# Kalibracija4.net
KiCad netlist of a schematic drawn in Altium Designer
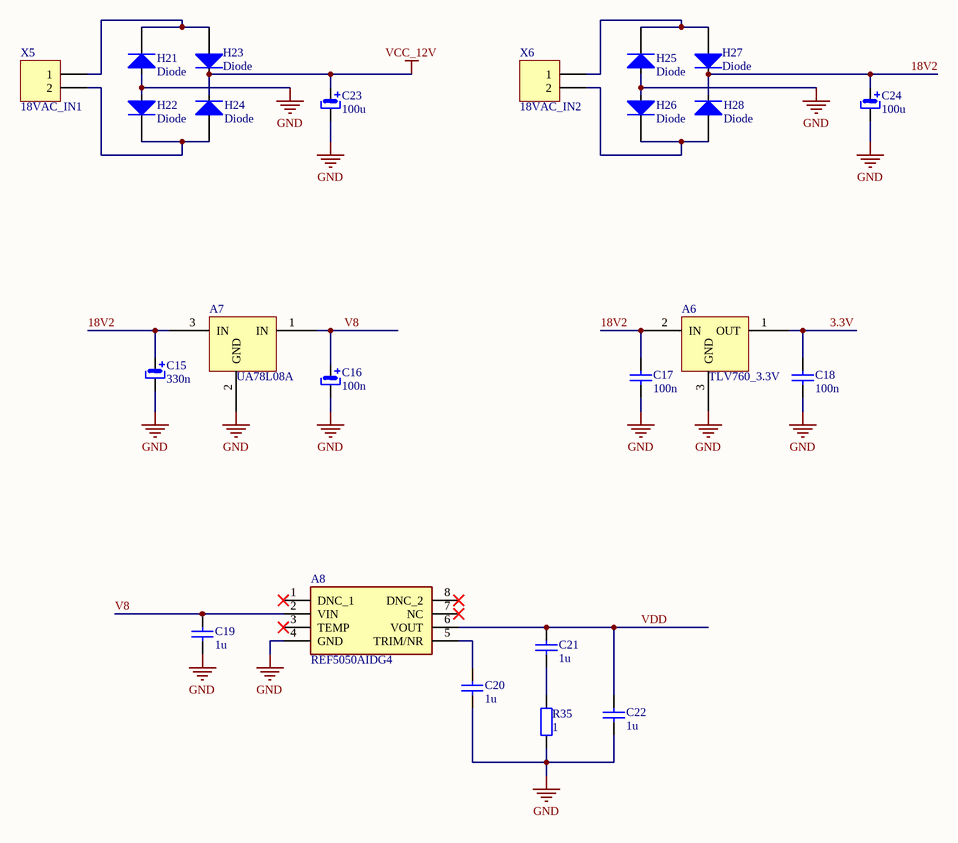
[diagram p0: Kalibracija4.SchDoc]

(export (version "E")
  (design (tool "Eeschema 10.0.6"))
  (components
    (comp (ref "A6") (value "TLV760_3.3V") (libsource (lib "Kalibracija") (part "TLV760")))
    (comp (ref "A7") (value "UA78L08A") (footprint "TO-92") (libsource (lib "Kalibracija") (part "UA78L08A")))
    (comp (ref "A8")
      (value "REF5050AIDG4")
      (footprint "SamacSys:SOIC127P600X175-8N")
      (description "Integrated Circuit")
      (fields (field (name "MOUSER PART NUMBER") "595-REF5050AIDG4"))
      (libsource (lib "*") (part "REF5050AIDG4"))
    )
    (comp (ref "C15") (value "330n") (libsource (lib "Kalibracija") (part "elko")))
    (comp (ref "C16") (value "100n") (libsource (lib "Kalibracija") (part "elko")))
    (comp (ref "C17")
      (value "100n")
      (footprint "6-0805_N")
      (description "Capacitor")
      (fields (field (name "PUBLISHER") "Altium Limited"))
      (libsource (lib "Miscellaneous Devices") (part "Cap"))
    )
    (comp (ref "C18")
      (value "100n")
      (footprint "6-0805_N")
      (description "Capacitor")
      (fields (field (name "PUBLISHER") "Altium Limited"))
      (libsource (lib "Miscellaneous Devices") (part "Cap"))
    )
    (comp (ref "C19")
      (value "1u")
      (footprint "6-0805_N")
      (description "Capacitor")
      (fields (field (name "PUBLISHER") "Altium Limited"))
      (libsource (lib "Miscellaneous Devices") (part "Cap"))
    )
    (comp (ref "C20")
      (value "1u")
      (footprint "6-0805_N")
      (description "Capacitor")
      (fields (field (name "PUBLISHER") "Altium Limited"))
      (libsource (lib "Miscellaneous Devices") (part "Cap"))
    )
    (comp (ref "C21")
      (value "1u")
      (footprint "6-0805_N")
      (description "Capacitor")
      (fields (field (name "PUBLISHER") "Altium Limited"))
      (libsource (lib "Miscellaneous Devices") (part "Cap"))
    )
    (comp (ref "C22")
      (value "1u")
      (footprint "6-0805_N")
      (description "Capacitor")
      (fields (field (name "PUBLISHER") "Altium Limited"))
      (libsource (lib "Miscellaneous Devices") (part "Cap"))
    )
    (comp (ref "C23") (value "100u") (libsource (lib "Kalibracija") (part "elko")))
    (comp (ref "C24") (value "100u") (libsource (lib "Kalibracija") (part "elko")))
    (comp (ref "H21")
      (value "Diode")
      (footprint "SMC")
      (description "Default Diode")
      (fields (field (name "PUBLISHER") "Altium Limited"))
      (libsource (lib "Miscellaneous Devices") (part "Diode"))
    )
    (comp (ref "H22")
      (value "Diode")
      (footprint "SMC")
      (description "Default Diode")
      (fields (field (name "PUBLISHER") "Altium Limited"))
      (libsource (lib "Miscellaneous Devices") (part "Diode"))
    )
    (comp (ref "H23")
      (value "Diode")
      (footprint "SMC")
      (description "Default Diode")
      (fields (field (name "PUBLISHER") "Altium Limited"))
      (libsource (lib "Miscellaneous Devices") (part "Diode"))
    )
    (comp (ref "H24")
      (value "Diode")
      (footprint "SMC")
      (description "Default Diode")
      (fields (field (name "PUBLISHER") "Altium Limited"))
      (libsource (lib "Miscellaneous Devices") (part "Diode"))
    )
    (comp (ref "H25")
      (value "Diode")
      (footprint "SMC")
      (description "Default Diode")
      (fields (field (name "PUBLISHER") "Altium Limited"))
      (libsource (lib "Miscellaneous Devices") (part "Diode"))
    )
    (comp (ref "H26")
      (value "Diode")
      (footprint "SMC")
      (description "Default Diode")
      (fields (field (name "PUBLISHER") "Altium Limited"))
      (libsource (lib "Miscellaneous Devices") (part "Diode"))
    )
    (comp (ref "H27")
      (value "Diode")
      (footprint "SMC")
      (description "Default Diode")
      (fields (field (name "PUBLISHER") "Altium Limited"))
      (libsource (lib "Miscellaneous Devices") (part "Diode"))
    )
    (comp (ref "H28")
      (value "Diode")
      (footprint "SMC")
      (description "Default Diode")
      (fields (field (name "PUBLISHER") "Altium Limited"))
      (libsource (lib "Miscellaneous Devices") (part "Diode"))
    )
    (comp (ref "R35")
      (value "1")
      (footprint "6-0805_N")
      (description "Resistor")
      (fields (field (name "PUBLISHER") "Altium Limited"))
      (libsource (lib "Miscellaneous Devices") (part "Res2"))
    )
    (comp (ref "X5")
      (value "18VAC_IN1")
      (footprint "HDR1X2")
      (description "Header, 2-Pin, Right Angle")
      (fields (field (name "PUBLISHER") "Altium Limited"))
      (libsource (lib "Miscellaneous Connectors") (part "Header 2H"))
    )
    (comp (ref "X6")
      (value "18VAC_IN2")
      (footprint "HDR1X2")
      (description "Header, 2-Pin, Right Angle")
      (fields (field (name "PUBLISHER") "Altium Limited"))
      (libsource (lib "Miscellaneous Connectors") (part "Header 2H"))
    )
  )
  (nets
    (net (code "1") (name "/3.3V") (class "Default")
      (node (ref "A6") (pin "1") (pinfunction "OUT_1") (pintype "power_in"))
      (node (ref "C18") (pin "2") (pinfunction "2_2") (pintype "passive"))
    )
    (net (code "2") (name "/18V2") (class "Default")
      (node (ref "A6") (pin "2") (pinfunction "IN_2") (pintype "passive"))
      (node (ref "A7") (pin "3") (pinfunction "IN_3") (pintype "power_in"))
      (node (ref "C15") (pin "1") (pinfunction "1_1") (pintype "passive"))
      (node (ref "C17") (pin "2") (pinfunction "2_2") (pintype "passive"))
      (node (ref "C24") (pin "1") (pinfunction "1_1") (pintype "passive"))
      (node (ref "H27") (pin "2") (pinfunction "K_2") (pintype "passive"))
      (node (ref "H28") (pin "2") (pinfunction "K_2") (pintype "passive"))
    )
    (net (code "3") (name "/V8") (class "Default")
      (node (ref "A7") (pin "1") (pinfunction "IN_1") (pintype "passive"))
      (node (ref "A8") (pin "2") (pinfunction "VIN_2") (pintype "passive"))
      (node (ref "C16") (pin "1") (pinfunction "1_1") (pintype "passive"))
      (node (ref "C19") (pin "2") (pinfunction "2_2") (pintype "passive"))
    )
    (net (code "4") (name "/VDD") (class "Default")
      (node (ref "A8") (pin "6") (pinfunction "VOUT_6") (pintype "passive"))
      (node (ref "C21") (pin "2") (pinfunction "2_2") (pintype "passive"))
      (node (ref "C22") (pin "2") (pinfunction "2_2") (pintype "passive"))
    )
    (net (code "5") (name "GND") (class "Default")
      (node (ref "A6") (pin "3") (pinfunction "GND_3") (pintype "power_in"))
      (node (ref "A7") (pin "2") (pinfunction "GND_2") (pintype "power_in"))
      (node (ref "A8") (pin "4") (pinfunction "GND_4") (pintype "passive"))
      (node (ref "C15") (pin "2") (pinfunction "2_2") (pintype "passive"))
      (node (ref "C16") (pin "2") (pinfunction "2_2") (pintype "passive"))
      (node (ref "C17") (pin "1") (pinfunction "1_1") (pintype "passive"))
      (node (ref "C18") (pin "1") (pinfunction "1_1") (pintype "passive"))
      (node (ref "C19") (pin "1") (pinfunction "1_1") (pintype "passive"))
      (node (ref "C20") (pin "1") (pinfunction "1_1") (pintype "passive"))
      (node (ref "C22") (pin "1") (pinfunction "1_1") (pintype "passive"))
      (node (ref "C23") (pin "2") (pinfunction "2_2") (pintype "passive"))
      (node (ref "C24") (pin "2") (pinfunction "2_2") (pintype "passive"))
      (node (ref "H21") (pin "1") (pinfunction "A_1") (pintype "passive"))
      (node (ref "H22") (pin "1") (pinfunction "A_1") (pintype "passive"))
      (node (ref "H25") (pin "1") (pinfunction "A_1") (pintype "passive"))
      (node (ref "H26") (pin "1") (pinfunction "A_1") (pintype "passive"))
      (node (ref "R35") (pin "1") (pinfunction "1_1") (pintype "passive"))
    )
    (net (code "6") (name "Net-(A8-TRIM{slash}NR)") (class "Default")
      (node (ref "A8") (pin "5") (pinfunction "TRIM/NR_5") (pintype "passive"))
      (node (ref "C20") (pin "2") (pinfunction "2_2") (pintype "passive"))
    )
    (net (code "7") (name "Net-(C21-Pad1)") (class "Default")
      (node (ref "C21") (pin "1") (pinfunction "1_1") (pintype "passive"))
      (node (ref "R35") (pin "2") (pinfunction "2_2") (pintype "passive"))
    )
    (net (code "8") (name "Net-(H21-K)") (class "Default")
      (node (ref "H21") (pin "2") (pinfunction "K_2") (pintype "passive"))
      (node (ref "H23") (pin "1") (pinfunction "A_1") (pintype "passive"))
      (node (ref "X5") (pin "1") (pinfunction "1_1") (pintype "passive"))
    )
    (net (code "9") (name "Net-(H22-K)") (class "Default")
      (node (ref "H22") (pin "2") (pinfunction "K_2") (pintype "passive"))
      (node (ref "H24") (pin "1") (pinfunction "A_1") (pintype "passive"))
      (node (ref "X5") (pin "2") (pinfunction "2_2") (pintype "passive"))
    )
    (net (code "10") (name "Net-(H25-K)") (class "Default")
      (node (ref "H25") (pin "2") (pinfunction "K_2") (pintype "passive"))
      (node (ref "H27") (pin "1") (pinfunction "A_1") (pintype "passive"))
      (node (ref "X6") (pin "1") (pinfunction "1_1") (pintype "passive"))
    )
    (net (code "11") (name "Net-(H26-K)") (class "Default")
      (node (ref "H26") (pin "2") (pinfunction "K_2") (pintype "passive"))
      (node (ref "H28") (pin "1") (pinfunction "A_1") (pintype "passive"))
      (node (ref "X6") (pin "2") (pinfunction "2_2") (pintype "passive"))
    )
    (net (code "12") (name "VCC_12V") (class "Default")
      (node (ref "C23") (pin "1") (pinfunction "1_1") (pintype "passive"))
      (node (ref "H23") (pin "2") (pinfunction "K_2") (pintype "passive"))
      (node (ref "H24") (pin "2") (pinfunction "K_2") (pintype "passive"))
    )
    (net (code "13") (name "unconnected-(A8-DNC_1-Pad1)") (class "Default")
      (node (ref "A8") (pin "1") (pinfunction "DNC_1_1") (pintype "passive+no_connect"))
    )
    (net (code "14") (name "unconnected-(A8-DNC_2-Pad8)") (class "Default")
      (node (ref "A8") (pin "8") (pinfunction "DNC_2_8") (pintype "passive+no_connect"))
    )
    (net (code "15") (name "unconnected-(A8-NC-Pad7)") (class "Default")
      (node (ref "A8") (pin "7") (pinfunction "NC_7") (pintype "passive+no_connect"))
    )
    (net (code "16") (name "unconnected-(A8-TEMP-Pad3)") (class "Default")
      (node (ref "A8") (pin "3") (pinfunction "TEMP_3") (pintype "passive+no_connect"))
    )
  )
)
